# tinynumitronboard-extended.net
KiCad netlist of a schematic drawn in EAGLE
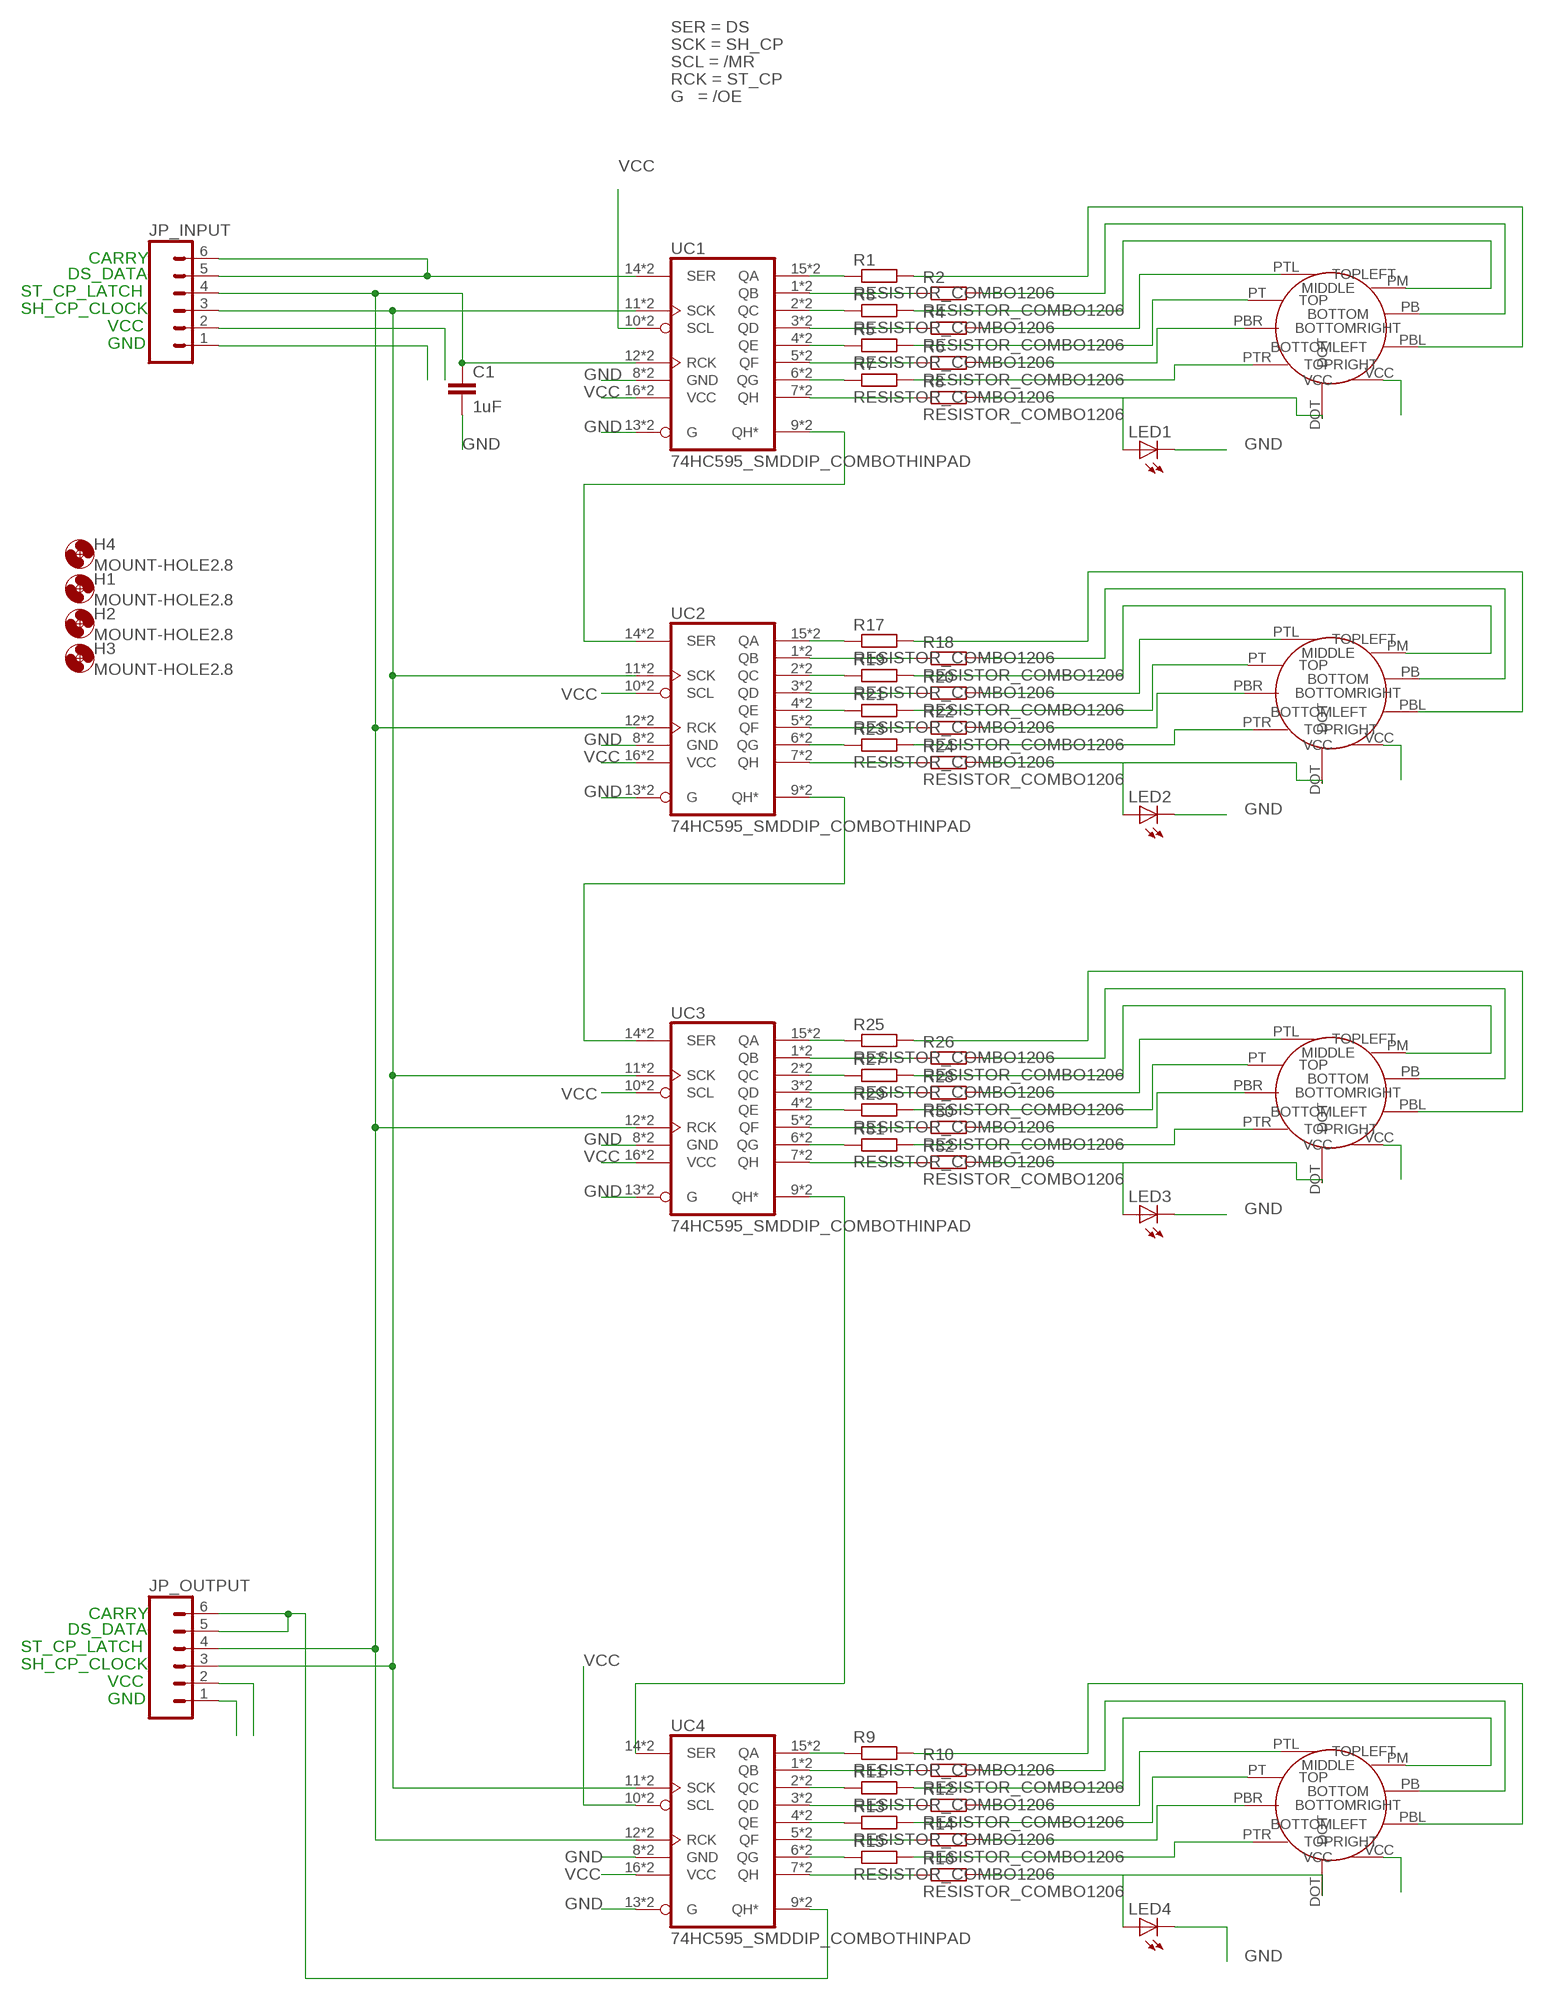
[diagram p0: schematic, sheet 1]

(export (version "E")
  (design (tool "Eeschema 10.0.6"))
  (components
    (comp (ref "C1")
      (value "1uF")
      (footprint "eagle-import:C050-024X044")
      (libsource (lib "eagle-import") (part "C-EU050-024X044"))
    )
    (comp (ref "H1")
      (value "MOUNT-HOLE2.8")
      (footprint "eagle-import:2,8")
      (libsource (lib "eagle-import") (part "MOUNT-HOLE2.8"))
    )
    (comp (ref "H2")
      (value "MOUNT-HOLE2.8")
      (footprint "eagle-import:2,8")
      (libsource (lib "eagle-import") (part "MOUNT-HOLE2.8"))
    )
    (comp (ref "H3")
      (value "MOUNT-HOLE2.8")
      (footprint "eagle-import:2,8")
      (libsource (lib "eagle-import") (part "MOUNT-HOLE2.8"))
    )
    (comp (ref "H4")
      (value "MOUNT-HOLE2.8")
      (footprint "eagle-import:2,8")
      (libsource (lib "eagle-import") (part "MOUNT-HOLE2.8"))
    )
    (comp (ref "JP_INPUT")
      (value "M06SIP")
      (footprint "eagle-import:1X06")
      (libsource (lib "eagle-import") (part "M06SIP"))
    )
    (comp (ref "JP_OUTPUT")
      (value "M06SIP")
      (footprint "eagle-import:1X06")
      (libsource (lib "eagle-import") (part "M06SIP"))
    )
    (comp (ref "LED1")
      (value "LEDKA-3528ASYC")
      (footprint "eagle-import:KA-3528ASYC")
      (libsource (lib "eagle-import") (part "LEDKA-3528ASYC"))
    )
    (comp (ref "LED2")
      (value "LEDKA-3528ASYC")
      (footprint "eagle-import:KA-3528ASYC")
      (libsource (lib "eagle-import") (part "LEDKA-3528ASYC"))
    )
    (comp (ref "LED3")
      (value "LEDKA-3528ASYC")
      (footprint "eagle-import:KA-3528ASYC")
      (libsource (lib "eagle-import") (part "LEDKA-3528ASYC"))
    )
    (comp (ref "LED4")
      (value "LEDKA-3528ASYC")
      (footprint "eagle-import:KA-3528ASYC")
      (libsource (lib "eagle-import") (part "LEDKA-3528ASYC"))
    )
    (comp (ref "R1")
      (value "RESISTOR_COMBO1206")
      (footprint "eagle-import:207-10_SMD_COMBO")
      (libsource (lib "eagle-import") (part "RESISTOR_COMBO1206"))
    )
    (comp (ref "R2")
      (value "RESISTOR_COMBO1206")
      (footprint "eagle-import:207-10_SMD_COMBO")
      (libsource (lib "eagle-import") (part "RESISTOR_COMBO1206"))
    )
    (comp (ref "R3")
      (value "RESISTOR_COMBO1206")
      (footprint "eagle-import:207-10_SMD_COMBO")
      (libsource (lib "eagle-import") (part "RESISTOR_COMBO1206"))
    )
    (comp (ref "R4")
      (value "RESISTOR_COMBO1206")
      (footprint "eagle-import:207-10_SMD_COMBO")
      (libsource (lib "eagle-import") (part "RESISTOR_COMBO1206"))
    )
    (comp (ref "R5")
      (value "RESISTOR_COMBO1206")
      (footprint "eagle-import:207-10_SMD_COMBO")
      (libsource (lib "eagle-import") (part "RESISTOR_COMBO1206"))
    )
    (comp (ref "R6")
      (value "RESISTOR_COMBO1206")
      (footprint "eagle-import:207-10_SMD_COMBO")
      (libsource (lib "eagle-import") (part "RESISTOR_COMBO1206"))
    )
    (comp (ref "R7")
      (value "RESISTOR_COMBO1206")
      (footprint "eagle-import:207-10_SMD_COMBO")
      (libsource (lib "eagle-import") (part "RESISTOR_COMBO1206"))
    )
    (comp (ref "R8")
      (value "RESISTOR_COMBO1206")
      (footprint "eagle-import:207-10_SMD_COMBO")
      (libsource (lib "eagle-import") (part "RESISTOR_COMBO1206"))
    )
    (comp (ref "R9")
      (value "RESISTOR_COMBO1206")
      (footprint "eagle-import:207-10_SMD_COMBO")
      (libsource (lib "eagle-import") (part "RESISTOR_COMBO1206"))
    )
    (comp (ref "R10")
      (value "RESISTOR_COMBO1206")
      (footprint "eagle-import:207-10_SMD_COMBO")
      (libsource (lib "eagle-import") (part "RESISTOR_COMBO1206"))
    )
    (comp (ref "R11")
      (value "RESISTOR_COMBO1206")
      (footprint "eagle-import:207-10_SMD_COMBO")
      (libsource (lib "eagle-import") (part "RESISTOR_COMBO1206"))
    )
    (comp (ref "R12")
      (value "RESISTOR_COMBO1206")
      (footprint "eagle-import:207-10_SMD_COMBO")
      (libsource (lib "eagle-import") (part "RESISTOR_COMBO1206"))
    )
    (comp (ref "R13")
      (value "RESISTOR_COMBO1206")
      (footprint "eagle-import:207-10_SMD_COMBO")
      (libsource (lib "eagle-import") (part "RESISTOR_COMBO1206"))
    )
    (comp (ref "R14")
      (value "RESISTOR_COMBO1206")
      (footprint "eagle-import:207-10_SMD_COMBO")
      (libsource (lib "eagle-import") (part "RESISTOR_COMBO1206"))
    )
    (comp (ref "R15")
      (value "RESISTOR_COMBO1206")
      (footprint "eagle-import:207-10_SMD_COMBO")
      (libsource (lib "eagle-import") (part "RESISTOR_COMBO1206"))
    )
    (comp (ref "R16")
      (value "RESISTOR_COMBO1206")
      (footprint "eagle-import:207-10_SMD_COMBO")
      (libsource (lib "eagle-import") (part "RESISTOR_COMBO1206"))
    )
    (comp (ref "R17")
      (value "RESISTOR_COMBO1206")
      (footprint "eagle-import:207-10_SMD_COMBO")
      (libsource (lib "eagle-import") (part "RESISTOR_COMBO1206"))
    )
    (comp (ref "R18")
      (value "RESISTOR_COMBO1206")
      (footprint "eagle-import:207-10_SMD_COMBO")
      (libsource (lib "eagle-import") (part "RESISTOR_COMBO1206"))
    )
    (comp (ref "R19")
      (value "RESISTOR_COMBO1206")
      (footprint "eagle-import:207-10_SMD_COMBO")
      (libsource (lib "eagle-import") (part "RESISTOR_COMBO1206"))
    )
    (comp (ref "R20")
      (value "RESISTOR_COMBO1206")
      (footprint "eagle-import:207-10_SMD_COMBO")
      (libsource (lib "eagle-import") (part "RESISTOR_COMBO1206"))
    )
    (comp (ref "R21")
      (value "RESISTOR_COMBO1206")
      (footprint "eagle-import:207-10_SMD_COMBO")
      (libsource (lib "eagle-import") (part "RESISTOR_COMBO1206"))
    )
    (comp (ref "R22")
      (value "RESISTOR_COMBO1206")
      (footprint "eagle-import:207-10_SMD_COMBO")
      (libsource (lib "eagle-import") (part "RESISTOR_COMBO1206"))
    )
    (comp (ref "R23")
      (value "RESISTOR_COMBO1206")
      (footprint "eagle-import:207-10_SMD_COMBO")
      (libsource (lib "eagle-import") (part "RESISTOR_COMBO1206"))
    )
    (comp (ref "R24")
      (value "RESISTOR_COMBO1206")
      (footprint "eagle-import:207-10_SMD_COMBO")
      (libsource (lib "eagle-import") (part "RESISTOR_COMBO1206"))
    )
    (comp (ref "R25")
      (value "RESISTOR_COMBO1206")
      (footprint "eagle-import:207-10_SMD_COMBO")
      (libsource (lib "eagle-import") (part "RESISTOR_COMBO1206"))
    )
    (comp (ref "R26")
      (value "RESISTOR_COMBO1206")
      (footprint "eagle-import:207-10_SMD_COMBO")
      (libsource (lib "eagle-import") (part "RESISTOR_COMBO1206"))
    )
    (comp (ref "R27")
      (value "RESISTOR_COMBO1206")
      (footprint "eagle-import:207-10_SMD_COMBO")
      (libsource (lib "eagle-import") (part "RESISTOR_COMBO1206"))
    )
    (comp (ref "R28")
      (value "RESISTOR_COMBO1206")
      (footprint "eagle-import:207-10_SMD_COMBO")
      (libsource (lib "eagle-import") (part "RESISTOR_COMBO1206"))
    )
    (comp (ref "R29")
      (value "RESISTOR_COMBO1206")
      (footprint "eagle-import:207-10_SMD_COMBO")
      (libsource (lib "eagle-import") (part "RESISTOR_COMBO1206"))
    )
    (comp (ref "R30")
      (value "RESISTOR_COMBO1206")
      (footprint "eagle-import:207-10_SMD_COMBO")
      (libsource (lib "eagle-import") (part "RESISTOR_COMBO1206"))
    )
    (comp (ref "R31")
      (value "RESISTOR_COMBO1206")
      (footprint "eagle-import:207-10_SMD_COMBO")
      (libsource (lib "eagle-import") (part "RESISTOR_COMBO1206"))
    )
    (comp (ref "R32")
      (value "RESISTOR_COMBO1206")
      (footprint "eagle-import:207-10_SMD_COMBO")
      (libsource (lib "eagle-import") (part "RESISTOR_COMBO1206"))
    )
    (comp (ref "U$1")
      (value "IV16TINY_NUMITRON")
      (footprint "eagle-import:IV16TINY_NUMITRON_PAC")
      (libsource (lib "eagle-import") (part "IV16TINY_NUMITRON"))
    )
    (comp (ref "U$2")
      (value "IV16TINY_NUMITRON")
      (footprint "eagle-import:IV16TINY_NUMITRON_PAC")
      (libsource (lib "eagle-import") (part "IV16TINY_NUMITRON"))
    )
    (comp (ref "U$5")
      (value "IV16TINY_NUMITRON")
      (footprint "eagle-import:IV16TINY_NUMITRON_PAC")
      (libsource (lib "eagle-import") (part "IV16TINY_NUMITRON"))
    )
    (comp (ref "U$7")
      (value "IV16TINY_NUMITRON")
      (footprint "eagle-import:IV16TINY_NUMITRON_PAC")
      (libsource (lib "eagle-import") (part "IV16TINY_NUMITRON"))
    )
    (comp (ref "UC1")
      (value "74HC595_SMDDIP_COMBOTHINPAD")
      (footprint "eagle-import:DIL16_SO16_PAC2")
      (libsource (lib "eagle-import") (part "74HC595_SMDDIP_COMBOTHINPAD"))
    )
    (comp (ref "UC2")
      (value "74HC595_SMDDIP_COMBOTHINPAD")
      (footprint "eagle-import:DIL16_SO16_PAC2")
      (libsource (lib "eagle-import") (part "74HC595_SMDDIP_COMBOTHINPAD"))
    )
    (comp (ref "UC3")
      (value "74HC595_SMDDIP_COMBOTHINPAD")
      (footprint "eagle-import:DIL16_SO16_PAC2")
      (libsource (lib "eagle-import") (part "74HC595_SMDDIP_COMBOTHINPAD"))
    )
    (comp (ref "UC4")
      (value "74HC595_SMDDIP_COMBOTHINPAD")
      (footprint "eagle-import:DIL16_SO16_PAC2")
      (libsource (lib "eagle-import") (part "74HC595_SMDDIP_COMBOTHINPAD"))
    )
  )
  (nets
    (net (code "1") (name "/GND") (class "Default")
      (node (ref "C1") (pin "2") (pinfunction "2_2") (pintype "passive"))
      (node (ref "JP_INPUT") (pin "1") (pinfunction "1_1") (pintype "passive"))
      (node (ref "JP_OUTPUT") (pin "1") (pinfunction "1_1") (pintype "passive"))
      (node (ref "LED1") (pin "C") (pinfunction "C_C") (pintype "passive"))
      (node (ref "LED2") (pin "C") (pinfunction "C_C") (pintype "passive"))
      (node (ref "LED3") (pin "C") (pinfunction "C_C") (pintype "passive"))
      (node (ref "LED4") (pin "C") (pinfunction "C_C") (pintype "passive"))
      (node (ref "UC1") (pin "13") (pinfunction "G_13") (pintype "input"))
      (node (ref "UC1") (pin "8") (pinfunction "GND_8") (pintype "power_in"))
      (node (ref "UC1") (pin "S13") (pinfunction "G_S13") (pintype "input"))
      (node (ref "UC1") (pin "S8") (pinfunction "GND_S8") (pintype "power_in"))
      (node (ref "UC2") (pin "13") (pinfunction "G_13") (pintype "input"))
      (node (ref "UC2") (pin "8") (pinfunction "GND_8") (pintype "power_in"))
      (node (ref "UC2") (pin "S13") (pinfunction "G_S13") (pintype "input"))
      (node (ref "UC2") (pin "S8") (pinfunction "GND_S8") (pintype "power_in"))
      (node (ref "UC3") (pin "13") (pinfunction "G_13") (pintype "input"))
      (node (ref "UC3") (pin "8") (pinfunction "GND_8") (pintype "power_in"))
      (node (ref "UC3") (pin "S13") (pinfunction "G_S13") (pintype "input"))
      (node (ref "UC3") (pin "S8") (pinfunction "GND_S8") (pintype "power_in"))
      (node (ref "UC4") (pin "13") (pinfunction "G_13") (pintype "input"))
      (node (ref "UC4") (pin "8") (pinfunction "GND_8") (pintype "power_in"))
      (node (ref "UC4") (pin "S13") (pinfunction "G_S13") (pintype "input"))
      (node (ref "UC4") (pin "S8") (pinfunction "GND_S8") (pintype "power_in"))
    )
    (net (code "2") (name "/VCC") (class "Default")
      (node (ref "JP_INPUT") (pin "2") (pinfunction "2_2") (pintype "passive"))
      (node (ref "JP_OUTPUT") (pin "2") (pinfunction "2_2") (pintype "passive"))
      (node (ref "U$1") (pin "VCC") (pinfunction "VCC_VCC") (pintype "input"))
      (node (ref "U$2") (pin "VCC") (pinfunction "VCC_VCC") (pintype "input"))
      (node (ref "U$5") (pin "VCC") (pinfunction "VCC_VCC") (pintype "input"))
      (node (ref "U$7") (pin "VCC") (pinfunction "VCC_VCC") (pintype "input"))
      (node (ref "UC1") (pin "10") (pinfunction "SCL_10") (pintype "input"))
      (node (ref "UC1") (pin "16") (pinfunction "VCC_16") (pintype "power_in"))
      (node (ref "UC1") (pin "S10") (pinfunction "SCL_S10") (pintype "input"))
      (node (ref "UC1") (pin "S16") (pinfunction "VCC_S16") (pintype "power_in"))
      (node (ref "UC2") (pin "10") (pinfunction "SCL_10") (pintype "input"))
      (node (ref "UC2") (pin "16") (pinfunction "VCC_16") (pintype "power_in"))
      (node (ref "UC2") (pin "S10") (pinfunction "SCL_S10") (pintype "input"))
      (node (ref "UC2") (pin "S16") (pinfunction "VCC_S16") (pintype "power_in"))
      (node (ref "UC3") (pin "10") (pinfunction "SCL_10") (pintype "input"))
      (node (ref "UC3") (pin "16") (pinfunction "VCC_16") (pintype "power_in"))
      (node (ref "UC3") (pin "S10") (pinfunction "SCL_S10") (pintype "input"))
      (node (ref "UC3") (pin "S16") (pinfunction "VCC_S16") (pintype "power_in"))
      (node (ref "UC4") (pin "10") (pinfunction "SCL_10") (pintype "input"))
      (node (ref "UC4") (pin "16") (pinfunction "VCC_16") (pintype "power_in"))
      (node (ref "UC4") (pin "S10") (pinfunction "SCL_S10") (pintype "input"))
      (node (ref "UC4") (pin "S16") (pinfunction "VCC_S16") (pintype "power_in"))
    )
    (net (code "3") (name "Net-(C1-Pad1)") (class "Default")
      (node (ref "C1") (pin "1") (pinfunction "1_1") (pintype "passive"))
      (node (ref "JP_INPUT") (pin "4") (pinfunction "4_4") (pintype "passive"))
      (node (ref "JP_OUTPUT") (pin "4") (pinfunction "4_4") (pintype "passive"))
      (node (ref "UC1") (pin "12") (pinfunction "RCK_12") (pintype "input"))
      (node (ref "UC1") (pin "S12") (pinfunction "RCK_S12") (pintype "input"))
      (node (ref "UC2") (pin "12") (pinfunction "RCK_12") (pintype "input"))
      (node (ref "UC2") (pin "S12") (pinfunction "RCK_S12") (pintype "input"))
      (node (ref "UC3") (pin "12") (pinfunction "RCK_12") (pintype "input"))
      (node (ref "UC3") (pin "S12") (pinfunction "RCK_S12") (pintype "input"))
      (node (ref "UC4") (pin "12") (pinfunction "RCK_12") (pintype "input"))
      (node (ref "UC4") (pin "S12") (pinfunction "RCK_S12") (pintype "input"))
    )
    (net (code "4") (name "Net-(JP_INPUT-Pad3)") (class "Default")
      (node (ref "JP_INPUT") (pin "3") (pinfunction "3_3") (pintype "passive"))
      (node (ref "JP_OUTPUT") (pin "3") (pinfunction "3_3") (pintype "passive"))
      (node (ref "UC1") (pin "11") (pinfunction "SCK_11") (pintype "input"))
      (node (ref "UC1") (pin "S11") (pinfunction "SCK_S11") (pintype "input"))
      (node (ref "UC2") (pin "11") (pinfunction "SCK_11") (pintype "input"))
      (node (ref "UC2") (pin "S11") (pinfunction "SCK_S11") (pintype "input"))
      (node (ref "UC3") (pin "11") (pinfunction "SCK_11") (pintype "input"))
      (node (ref "UC3") (pin "S11") (pinfunction "SCK_S11") (pintype "input"))
      (node (ref "UC4") (pin "11") (pinfunction "SCK_11") (pintype "input"))
      (node (ref "UC4") (pin "S11") (pinfunction "SCK_S11") (pintype "input"))
    )
    (net (code "5") (name "Net-(JP_INPUT-Pad5)") (class "Default")
      (node (ref "JP_INPUT") (pin "5") (pinfunction "5_5") (pintype "passive"))
      (node (ref "JP_INPUT") (pin "6") (pinfunction "6_6") (pintype "passive"))
      (node (ref "UC1") (pin "14") (pinfunction "SER_14") (pintype "input"))
      (node (ref "UC1") (pin "S14") (pinfunction "SER_S14") (pintype "input"))
    )
    (net (code "6") (name "Net-(JP_OUTPUT-Pad5)") (class "Default")
      (node (ref "JP_OUTPUT") (pin "5") (pinfunction "5_5") (pintype "passive"))
      (node (ref "JP_OUTPUT") (pin "6") (pinfunction "6_6") (pintype "passive"))
      (node (ref "UC4") (pin "9") (pinfunction "QH*_9") (pintype "tri_state"))
      (node (ref "UC4") (pin "S9") (pinfunction "QH*_S9") (pintype "tri_state"))
    )
    (net (code "7") (name "Net-(LED1-PadA)") (class "Default")
      (node (ref "LED1") (pin "A") (pinfunction "A_A") (pintype "passive"))
      (node (ref "R8") (pin "2") (pinfunction "2_2") (pintype "passive"))
      (node (ref "R8") (pin "3") (pinfunction "2_3") (pintype "passive"))
      (node (ref "U$1") (pin "DOT") (pinfunction "DOT_DOT") (pintype "bidirectional"))
    )
    (net (code "8") (name "Net-(LED2-PadA)") (class "Default")
      (node (ref "LED2") (pin "A") (pinfunction "A_A") (pintype "passive"))
      (node (ref "R24") (pin "2") (pinfunction "2_2") (pintype "passive"))
      (node (ref "R24") (pin "3") (pinfunction "2_3") (pintype "passive"))
      (node (ref "U$5") (pin "DOT") (pinfunction "DOT_DOT") (pintype "bidirectional"))
    )
    (net (code "9") (name "Net-(LED3-PadA)") (class "Default")
      (node (ref "LED3") (pin "A") (pinfunction "A_A") (pintype "passive"))
      (node (ref "R32") (pin "2") (pinfunction "2_2") (pintype "passive"))
      (node (ref "R32") (pin "3") (pinfunction "2_3") (pintype "passive"))
      (node (ref "U$7") (pin "DOT") (pinfunction "DOT_DOT") (pintype "bidirectional"))
    )
    (net (code "10") (name "Net-(LED4-PadA)") (class "Default")
      (node (ref "LED4") (pin "A") (pinfunction "A_A") (pintype "passive"))
      (node (ref "R16") (pin "2") (pinfunction "2_2") (pintype "passive"))
      (node (ref "R16") (pin "3") (pinfunction "2_3") (pintype "passive"))
      (node (ref "U$2") (pin "DOT") (pinfunction "DOT_DOT") (pintype "bidirectional"))
    )
    (net (code "11") (name "Net-(R1-1-Pad4)") (class "Default")
      (node (ref "R1") (pin "1") (pinfunction "1_1") (pintype "passive"))
      (node (ref "R1") (pin "4") (pinfunction "1_4") (pintype "passive"))
      (node (ref "UC1") (pin "15") (pinfunction "QA_15") (pintype "tri_state"))
      (node (ref "UC1") (pin "S15") (pinfunction "QA_S15") (pintype "tri_state"))
    )
    (net (code "12") (name "Net-(R2-1-Pad4)") (class "Default")
      (node (ref "R2") (pin "1") (pinfunction "1_1") (pintype "passive"))
      (node (ref "R2") (pin "4") (pinfunction "1_4") (pintype "passive"))
      (node (ref "UC1") (pin "1") (pinfunction "QB_1") (pintype "tri_state"))
      (node (ref "UC1") (pin "S1") (pinfunction "QB_S1") (pintype "tri_state"))
    )
    (net (code "13") (name "Net-(R3-1-Pad4)") (class "Default")
      (node (ref "R3") (pin "1") (pinfunction "1_1") (pintype "passive"))
      (node (ref "R3") (pin "4") (pinfunction "1_4") (pintype "passive"))
      (node (ref "UC1") (pin "2") (pinfunction "QC_2") (pintype "tri_state"))
      (node (ref "UC1") (pin "S2") (pinfunction "QC_S2") (pintype "tri_state"))
    )
    (net (code "14") (name "Net-(R4-1-Pad4)") (class "Default")
      (node (ref "R4") (pin "1") (pinfunction "1_1") (pintype "passive"))
      (node (ref "R4") (pin "4") (pinfunction "1_4") (pintype "passive"))
      (node (ref "UC1") (pin "3") (pinfunction "QD_3") (pintype "tri_state"))
      (node (ref "UC1") (pin "S3") (pinfunction "QD_S3") (pintype "tri_state"))
    )
    (net (code "15") (name "Net-(R5-1-Pad4)") (class "Default")
      (node (ref "R5") (pin "1") (pinfunction "1_1") (pintype "passive"))
      (node (ref "R5") (pin "4") (pinfunction "1_4") (pintype "passive"))
      (node (ref "UC1") (pin "4") (pinfunction "QE_4") (pintype "tri_state"))
      (node (ref "UC1") (pin "S4") (pinfunction "QE_S4") (pintype "tri_state"))
    )
    (net (code "16") (name "Net-(R6-1-Pad4)") (class "Default")
      (node (ref "R6") (pin "1") (pinfunction "1_1") (pintype "passive"))
      (node (ref "R6") (pin "4") (pinfunction "1_4") (pintype "passive"))
      (node (ref "UC1") (pin "5") (pinfunction "QF_5") (pintype "tri_state"))
      (node (ref "UC1") (pin "S5") (pinfunction "QF_S5") (pintype "tri_state"))
    )
    (net (code "17") (name "Net-(R7-1-Pad4)") (class "Default")
      (node (ref "R7") (pin "1") (pinfunction "1_1") (pintype "passive"))
      (node (ref "R7") (pin "4") (pinfunction "1_4") (pintype "passive"))
      (node (ref "UC1") (pin "6") (pinfunction "QG_6") (pintype "tri_state"))
      (node (ref "UC1") (pin "S6") (pinfunction "QG_S6") (pintype "tri_state"))
    )
    (net (code "18") (name "Net-(R8-1-Pad4)") (class "Default")
      (node (ref "R8") (pin "1") (pinfunction "1_1") (pintype "passive"))
      (node (ref "R8") (pin "4") (pinfunction "1_4") (pintype "passive"))
      (node (ref "UC1") (pin "7") (pinfunction "QH_7") (pintype "tri_state"))
      (node (ref "UC1") (pin "S7") (pinfunction "QH_S7") (pintype "tri_state"))
    )
    (net (code "19") (name "Net-(R9-1-Pad4)") (class "Default")
      (node (ref "R9") (pin "1") (pinfunction "1_1") (pintype "passive"))
      (node (ref "R9") (pin "4") (pinfunction "1_4") (pintype "passive"))
      (node (ref "UC4") (pin "15") (pinfunction "QA_15") (pintype "tri_state"))
      (node (ref "UC4") (pin "S15") (pinfunction "QA_S15") (pintype "tri_state"))
    )
    (net (code "20") (name "Net-(R10-1-Pad4)") (class "Default")
      (node (ref "R10") (pin "1") (pinfunction "1_1") (pintype "passive"))
      (node (ref "R10") (pin "4") (pinfunction "1_4") (pintype "passive"))
      (node (ref "UC4") (pin "1") (pinfunction "QB_1") (pintype "tri_state"))
      (node (ref "UC4") (pin "S1") (pinfunction "QB_S1") (pintype "tri_state"))
    )
    (net (code "21") (name "Net-(R11-1-Pad4)") (class "Default")
      (node (ref "R11") (pin "1") (pinfunction "1_1") (pintype "passive"))
      (node (ref "R11") (pin "4") (pinfunction "1_4") (pintype "passive"))
      (node (ref "UC4") (pin "2") (pinfunction "QC_2") (pintype "tri_state"))
      (node (ref "UC4") (pin "S2") (pinfunction "QC_S2") (pintype "tri_state"))
    )
    (net (code "22") (name "Net-(R12-1-Pad4)") (class "Default")
      (node (ref "R12") (pin "1") (pinfunction "1_1") (pintype "passive"))
      (node (ref "R12") (pin "4") (pinfunction "1_4") (pintype "passive"))
      (node (ref "UC4") (pin "3") (pinfunction "QD_3") (pintype "tri_state"))
      (node (ref "UC4") (pin "S3") (pinfunction "QD_S3") (pintype "tri_state"))
    )
    (net (code "23") (name "Net-(R13-1-Pad4)") (class "Default")
      (node (ref "R13") (pin "1") (pinfunction "1_1") (pintype "passive"))
      (node (ref "R13") (pin "4") (pinfunction "1_4") (pintype "passive"))
      (node (ref "UC4") (pin "4") (pinfunction "QE_4") (pintype "tri_state"))
      (node (ref "UC4") (pin "S4") (pinfunction "QE_S4") (pintype "tri_state"))
    )
    (net (code "24") (name "Net-(R14-1-Pad4)") (class "Default")
      (node (ref "R14") (pin "1") (pinfunction "1_1") (pintype "passive"))
      (node (ref "R14") (pin "4") (pinfunction "1_4") (pintype "passive"))
      (node (ref "UC4") (pin "5") (pinfunction "QF_5") (pintype "tri_state"))
      (node (ref "UC4") (pin "S5") (pinfunction "QF_S5") (pintype "tri_state"))
    )
    (net (code "25") (name "Net-(R15-1-Pad4)") (class "Default")
      (node (ref "R15") (pin "1") (pinfunction "1_1") (pintype "passive"))
      (node (ref "R15") (pin "4") (pinfunction "1_4") (pintype "passive"))
      (node (ref "UC4") (pin "6") (pinfunction "QG_6") (pintype "tri_state"))
      (node (ref "UC4") (pin "S6") (pinfunction "QG_S6") (pintype "tri_state"))
    )
    (net (code "26") (name "Net-(R16-1-Pad4)") (class "Default")
      (node (ref "R16") (pin "1") (pinfunction "1_1") (pintype "passive"))
      (node (ref "R16") (pin "4") (pinfunction "1_4") (pintype "passive"))
      (node (ref "UC4") (pin "7") (pinfunction "QH_7") (pintype "tri_state"))
      (node (ref "UC4") (pin "S7") (pinfunction "QH_S7") (pintype "tri_state"))
    )
    (net (code "27") (name "Net-(R17-1-Pad4)") (class "Default")
      (node (ref "R17") (pin "1") (pinfunction "1_1") (pintype "passive"))
      (node (ref "R17") (pin "4") (pinfunction "1_4") (pintype "passive"))
      (node (ref "UC2") (pin "15") (pinfunction "QA_15") (pintype "tri_state"))
      (node (ref "UC2") (pin "S15") (pinfunction "QA_S15") (pintype "tri_state"))
    )
    (net (code "28") (name "Net-(R18-1-Pad4)") (class "Default")
      (node (ref "R18") (pin "1") (pinfunction "1_1") (pintype "passive"))
      (node (ref "R18") (pin "4") (pinfunction "1_4") (pintype "passive"))
      (node (ref "UC2") (pin "1") (pinfunction "QB_1") (pintype "tri_state"))
      (node (ref "UC2") (pin "S1") (pinfunction "QB_S1") (pintype "tri_state"))
    )
    (net (code "29") (name "Net-(R19-1-Pad4)") (class "Default")
      (node (ref "R19") (pin "1") (pinfunction "1_1") (pintype "passive"))
      (node (ref "R19") (pin "4") (pinfunction "1_4") (pintype "passive"))
      (node (ref "UC2") (pin "2") (pinfunction "QC_2") (pintype "tri_state"))
      (node (ref "UC2") (pin "S2") (pinfunction "QC_S2") (pintype "tri_state"))
    )
    (net (code "30") (name "Net-(R20-1-Pad4)") (class "Default")
      (node (ref "R20") (pin "1") (pinfunction "1_1") (pintype "passive"))
      (node (ref "R20") (pin "4") (pinfunction "1_4") (pintype "passive"))
      (node (ref "UC2") (pin "3") (pinfunction "QD_3") (pintype "tri_state"))
      (node (ref "UC2") (pin "S3") (pinfunction "QD_S3") (pintype "tri_state"))
    )
    (net (code "31") (name "Net-(R21-1-Pad4)") (class "Default")
      (node (ref "R21") (pin "1") (pinfunction "1_1") (pintype "passive"))
      (node (ref "R21") (pin "4") (pinfunction "1_4") (pintype "passive"))
      (node (ref "UC2") (pin "4") (pinfunction "QE_4") (pintype "tri_state"))
      (node (ref "UC2") (pin "S4") (pinfunction "QE_S4") (pintype "tri_state"))
    )
    (net (code "32") (name "Net-(R22-1-Pad4)") (class "Default")
      (node (ref "R22") (pin "1") (pinfunction "1_1") (pintype "passive"))
      (node (ref "R22") (pin "4") (pinfunction "1_4") (pintype "passive"))
      (node (ref "UC2") (pin "5") (pinfunction "QF_5") (pintype "tri_state"))
      (node (ref "UC2") (pin "S5") (pinfunction "QF_S5") (pintype "tri_state"))
    )
    (net (code "33") (name "Net-(R23-1-Pad4)") (class "Default")
      (node (ref "R23") (pin "1") (pinfunction "1_1") (pintype "passive"))
      (node (ref "R23") (pin "4") (pinfunction "1_4") (pintype "passive"))
      (node (ref "UC2") (pin "6") (pinfunction "QG_6") (pintype "tri_state"))
      (node (ref "UC2") (pin "S6") (pinfunction "QG_S6") (pintype "tri_state"))
    )
    (net (code "34") (name "Net-(R24-1-Pad4)") (class "Default")
      (node (ref "R24") (pin "1") (pinfunction "1_1") (pintype "passive"))
      (node (ref "R24") (pin "4") (pinfunction "1_4") (pintype "passive"))
      (node (ref "UC2") (pin "7") (pinfunction "QH_7") (pintype "tri_state"))
      (node (ref "UC2") (pin "S7") (pinfunction "QH_S7") (pintype "tri_state"))
    )
    (net (code "35") (name "Net-(R25-1-Pad4)") (class "Default")
      (node (ref "R25") (pin "1") (pinfunction "1_1") (pintype "passive"))
      (node (ref "R25") (pin "4") (pinfunction "1_4") (pintype "passive"))
      (node (ref "UC3") (pin "15") (pinfunction "QA_15") (pintype "tri_state"))
      (node (ref "UC3") (pin "S15") (pinfunction "QA_S15") (pintype "tri_state"))
    )
    (net (code "36") (name "Net-(R26-1-Pad4)") (class "Default")
      (node (ref "R26") (pin "1") (pinfunction "1_1") (pintype "passive"))
      (node (ref "R26") (pin "4") (pinfunction "1_4") (pintype "passive"))
      (node (ref "UC3") (pin "1") (pinfunction "QB_1") (pintype "tri_state"))
      (node (ref "UC3") (pin "S1") (pinfunction "QB_S1") (pintype "tri_state"))
    )
    (net (code "37") (name "Net-(R27-1-Pad4)") (class "Default")
      (node (ref "R27") (pin "1") (pinfunction "1_1") (pintype "passive"))
      (node (ref "R27") (pin "4") (pinfunction "1_4") (pintype "passive"))
      (node (ref "UC3") (pin "2") (pinfunction "QC_2") (pintype "tri_state"))
      (node (ref "UC3") (pin "S2") (pinfunction "QC_S2") (pintype "tri_state"))
    )
    (net (code "38") (name "Net-(R28-1-Pad4)") (class "Default")
      (node (ref "R28") (pin "1") (pinfunction "1_1") (pintype "passive"))
      (node (ref "R28") (pin "4") (pinfunction "1_4") (pintype "passive"))
      (node (ref "UC3") (pin "3") (pinfunction "QD_3") (pintype "tri_state"))
      (node (ref "UC3") (pin "S3") (pinfunction "QD_S3") (pintype "tri_state"))
    )
    (net (code "39") (name "Net-(R29-1-Pad4)") (class "Default")
      (node (ref "R29") (pin "1") (pinfunction "1_1") (pintype "passive"))
      (node (ref "R29") (pin "4") (pinfunction "1_4") (pintype "passive"))
      (node (ref "UC3") (pin "4") (pinfunction "QE_4") (pintype "tri_state"))
      (node (ref "UC3") (pin "S4") (pinfunction "QE_S4") (pintype "tri_state"))
    )
    (net (code "40") (name "Net-(R30-1-Pad4)") (class "Default")
      (node (ref "R30") (pin "1") (pinfunction "1_1") (pintype "passive"))
      (node (ref "R30") (pin "4") (pinfunction "1_4") (pintype "passive"))
      (node (ref "UC3") (pin "5") (pinfunction "QF_5") (pintype "tri_state"))
      (node (ref "UC3") (pin "S5") (pinfunction "QF_S5") (pintype "tri_state"))
    )
    (net (code "41") (name "Net-(R31-1-Pad4)") (class "Default")
      (node (ref "R31") (pin "1") (pinfunction "1_1") (pintype "passive"))
      (node (ref "R31") (pin "4") (pinfunction "1_4") (pintype "passive"))
      (node (ref "UC3") (pin "6") (pinfunction "QG_6") (pintype "tri_state"))
      (node (ref "UC3") (pin "S6") (pinfunction "QG_S6") (pintype "tri_state"))
    )
    (net (code "42") (name "Net-(R32-1-Pad4)") (class "Default")
      (node (ref "R32") (pin "1") (pinfunction "1_1") (pintype "passive"))
      (node (ref "R32") (pin "4") (pinfunction "1_4") (pintype "passive"))
      (node (ref "UC3") (pin "7") (pinfunction "QH_7") (pintype "tri_state"))
      (node (ref "UC3") (pin "S7") (pinfunction "QH_S7") (pintype "tri_state"))
    )
    (net (code "43") (name "Net-(U$1-BOTTOM)") (class "Default")
      (node (ref "R2") (pin "2") (pinfunction "2_2") (pintype "passive"))
      (node (ref "R2") (pin "3") (pinfunction "2_3") (pintype "passive"))
      (node (ref "U$1") (pin "PB") (pinfunction "BOTTOM_PB") (pintype "input"))
    )
    (net (code "44") (name "Net-(U$1-BOTTOMLEFT)") (class "Default")
      (node (ref "R1") (pin "2") (pinfunction "2_2") (pintype "passive"))
      (node (ref "R1") (pin "3") (pinfunction "2_3") (pintype "passive"))
      (node (ref "U$1") (pin "PBL") (pinfunction "BOTTOMLEFT_PBL") (pintype "input"))
    )
    (net (code "45") (name "Net-(U$1-BOTTOMRIGHT)") (class "Default")
      (node (ref "R6") (pin "2") (pinfunction "2_2") (pintype "passive"))
      (node (ref "R6") (pin "3") (pinfunction "2_3") (pintype "passive"))
      (node (ref "U$1") (pin "PBR") (pinfunction "BOTTOMRIGHT_PBR") (pintype "input"))
    )
    (net (code "46") (name "Net-(U$1-MIDDLE)") (class "Default")
      (node (ref "R3") (pin "2") (pinfunction "2_2") (pintype "passive"))
      (node (ref "R3") (pin "3") (pinfunction "2_3") (pintype "passive"))
      (node (ref "U$1") (pin "PM") (pinfunction "MIDDLE_PM") (pintype "input"))
    )
    (net (code "47") (name "Net-(U$1-TOP)") (class "Default")
      (node (ref "R5") (pin "2") (pinfunction "2_2") (pintype "passive"))
      (node (ref "R5") (pin "3") (pinfunction "2_3") (pintype "passive"))
      (node (ref "U$1") (pin "PT") (pinfunction "TOP_PT") (pintype "input"))
    )
    (net (code "48") (name "Net-(U$1-TOPLEFT)") (class "Default")
      (node (ref "R4") (pin "2") (pinfunction "2_2") (pintype "passive"))
      (node (ref "R4") (pin "3") (pinfunction "2_3") (pintype "passive"))
      (node (ref "U$1") (pin "PTL") (pinfunction "TOPLEFT_PTL") (pintype "input"))
    )
    (net (code "49") (name "Net-(U$1-TOPRIGHT)") (class "Default")
      (node (ref "R7") (pin "2") (pinfunction "2_2") (pintype "passive"))
      (node (ref "R7") (pin "3") (pinfunction "2_3") (pintype "passive"))
      (node (ref "U$1") (pin "PTR") (pinfunction "TOPRIGHT_PTR") (pintype "input"))
    )
    (net (code "50") (name "Net-(U$2-BOTTOM)") (class "Default")
      (node (ref "R10") (pin "2") (pinfunction "2_2") (pintype "passive"))
      (node (ref "R10") (pin "3") (pinfunction "2_3") (pintype "passive"))
      (node (ref "U$2") (pin "PB") (pinfunction "BOTTOM_PB") (pintype "input"))
    )
    (net (code "51") (name "Net-(U$2-BOTTOMLEFT)") (class "Default")
      (node (ref "R9") (pin "2") (pinfunction "2_2") (pintype "passive"))
      (node (ref "R9") (pin "3") (pinfunction "2_3") (pintype "passive"))
      (node (ref "U$2") (pin "PBL") (pinfunction "BOTTOMLEFT_PBL") (pintype "input"))
    )
    (net (code "52") (name "Net-(U$2-BOTTOMRIGHT)") (class "Default")
      (node (ref "R14") (pin "2") (pinfunction "2_2") (pintype "passive"))
      (node (ref "R14") (pin "3") (pinfunction "2_3") (pintype "passive"))
      (node (ref "U$2") (pin "PBR") (pinfunction "BOTTOMRIGHT_PBR") (pintype "input"))
    )
    (net (code "53") (name "Net-(U$2-MIDDLE)") (class "Default")
      (node (ref "R11") (pin "2") (pinfunction "2_2") (pintype "passive"))
      (node (ref "R11") (pin "3") (pinfunction "2_3") (pintype "passive"))
      (node (ref "U$2") (pin "PM") (pinfunction "MIDDLE_PM") (pintype "input"))
    )
    (net (code "54") (name "Net-(U$2-TOP)") (class "Default")
      (node (ref "R13") (pin "2") (pinfunction "2_2") (pintype "passive"))
      (node (ref "R13") (pin "3") (pinfunction "2_3") (pintype "passive"))
      (node (ref "U$2") (pin "PT") (pinfunction "TOP_PT") (pintype "input"))
    )
    (net (code "55") (name "Net-(U$2-TOPLEFT)") (class "Default")
      (node (ref "R12") (pin "2") (pinfunction "2_2") (pintype "passive"))
      (node (ref "R12") (pin "3") (pinfunction "2_3") (pintype "passive"))
      (node (ref "U$2") (pin "PTL") (pinfunction "TOPLEFT_PTL") (pintype "input"))
    )
    (net (code "56") (name "Net-(U$2-TOPRIGHT)") (class "Default")
      (node (ref "R15") (pin "2") (pinfunction "2_2") (pintype "passive"))
      (node (ref "R15") (pin "3") (pinfunction "2_3") (pintype "passive"))
      (node (ref "U$2") (pin "PTR") (pinfunction "TOPRIGHT_PTR") (pintype "input"))
    )
    (net (code "57") (name "Net-(U$5-BOTTOM)") (class "Default")
      (node (ref "R18") (pin "2") (pinfunction "2_2") (pintype "passive"))
      (node (ref "R18") (pin "3") (pinfunction "2_3") (pintype "passive"))
      (node (ref "U$5") (pin "PB") (pinfunction "BOTTOM_PB") (pintype "input"))
    )
    (net (code "58") (name "Net-(U$5-BOTTOMLEFT)") (class "Default")
      (node (ref "R17") (pin "2") (pinfunction "2_2") (pintype "passive"))
      (node (ref "R17") (pin "3") (pinfunction "2_3") (pintype "passive"))
      (node (ref "U$5") (pin "PBL") (pinfunction "BOTTOMLEFT_PBL") (pintype "input"))
    )
    (net (code "59") (name "Net-(U$5-BOTTOMRIGHT)") (class "Default")
      (node (ref "R22") (pin "2") (pinfunction "2_2") (pintype "passive"))
      (node (ref "R22") (pin "3") (pinfunction "2_3") (pintype "passive"))
      (node (ref "U$5") (pin "PBR") (pinfunction "BOTTOMRIGHT_PBR") (pintype "input"))
    )
    (net (code "60") (name "Net-(U$5-MIDDLE)") (class "Default")
      (node (ref "R19") (pin "2") (pinfunction "2_2") (pintype "passive"))
      (node (ref "R19") (pin "3") (pinfunction "2_3") (pintype "passive"))
      (node (ref "U$5") (pin "PM") (pinfunction "MIDDLE_PM") (pintype "input"))
    )
    (net (code "61") (name "Net-(U$5-TOP)") (class "Default")
      (node (ref "R21") (pin "2") (pinfunction "2_2") (pintype "passive"))
      (node (ref "R21") (pin "3") (pinfunction "2_3") (pintype "passive"))
      (node (ref "U$5") (pin "PT") (pinfunction "TOP_PT") (pintype "input"))
    )
    (net (code "62") (name "Net-(U$5-TOPLEFT)") (class "Default")
      (node (ref "R20") (pin "2") (pinfunction "2_2") (pintype "passive"))
      (node (ref "R20") (pin "3") (pinfunction "2_3") (pintype "passive"))
      (node (ref "U$5") (pin "PTL") (pinfunction "TOPLEFT_PTL") (pintype "input"))
    )
    (net (code "63") (name "Net-(U$5-TOPRIGHT)") (class "Default")
      (node (ref "R23") (pin "2") (pinfunction "2_2") (pintype "passive"))
      (node (ref "R23") (pin "3") (pinfunction "2_3") (pintype "passive"))
      (node (ref "U$5") (pin "PTR") (pinfunction "TOPRIGHT_PTR") (pintype "input"))
    )
    (net (code "64") (name "Net-(U$7-BOTTOM)") (class "Default")
      (node (ref "R26") (pin "2") (pinfunction "2_2") (pintype "passive"))
      (node (ref "R26") (pin "3") (pinfunction "2_3") (pintype "passive"))
      (node (ref "U$7") (pin "PB") (pinfunction "BOTTOM_PB") (pintype "input"))
    )
    (net (code "65") (name "Net-(U$7-BOTTOMLEFT)") (class "Default")
      (node (ref "R25") (pin "2") (pinfunction "2_2") (pintype "passive"))
      (node (ref "R25") (pin "3") (pinfunction "2_3") (pintype "passive"))
      (node (ref "U$7") (pin "PBL") (pinfunction "BOTTOMLEFT_PBL") (pintype "input"))
    )
    (net (code "66") (name "Net-(U$7-BOTTOMRIGHT)") (class "Default")
      (node (ref "R30") (pin "2") (pinfunction "2_2") (pintype "passive"))
      (node (ref "R30") (pin "3") (pinfunction "2_3") (pintype "passive"))
      (node (ref "U$7") (pin "PBR") (pinfunction "BOTTOMRIGHT_PBR") (pintype "input"))
    )
    (net (code "67") (name "Net-(U$7-MIDDLE)") (class "Default")
      (node (ref "R27") (pin "2") (pinfunction "2_2") (pintype "passive"))
      (node (ref "R27") (pin "3") (pinfunction "2_3") (pintype "passive"))
      (node (ref "U$7") (pin "PM") (pinfunction "MIDDLE_PM") (pintype "input"))
    )
    (net (code "68") (name "Net-(U$7-TOP)") (class "Default")
      (node (ref "R29") (pin "2") (pinfunction "2_2") (pintype "passive"))
      (node (ref "R29") (pin "3") (pinfunction "2_3") (pintype "passive"))
      (node (ref "U$7") (pin "PT") (pinfunction "TOP_PT") (pintype "input"))
    )
    (net (code "69") (name "Net-(U$7-TOPLEFT)") (class "Default")
      (node (ref "R28") (pin "2") (pinfunction "2_2") (pintype "passive"))
      (node (ref "R28") (pin "3") (pinfunction "2_3") (pintype "passive"))
      (node (ref "U$7") (pin "PTL") (pinfunction "TOPLEFT_PTL") (pintype "input"))
    )
    (net (code "70") (name "Net-(U$7-TOPRIGHT)") (class "Default")
      (node (ref "R31") (pin "2") (pinfunction "2_2") (pintype "passive"))
      (node (ref "R31") (pin "3") (pinfunction "2_3") (pintype "passive"))
      (node (ref "U$7") (pin "PTR") (pinfunction "TOPRIGHT_PTR") (pintype "input"))
    )
    (net (code "71") (name "Net-(UC1-QH*-Pad9)") (class "Default")
      (node (ref "UC1") (pin "9") (pinfunction "QH*_9") (pintype "tri_state"))
      (node (ref "UC1") (pin "S9") (pinfunction "QH*_S9") (pintype "tri_state"))
      (node (ref "UC2") (pin "14") (pinfunction "SER_14") (pintype "input"))
      (node (ref "UC2") (pin "S14") (pinfunction "SER_S14") (pintype "input"))
    )
    (net (code "72") (name "Net-(UC2-QH*-Pad9)") (class "Default")
      (node (ref "UC2") (pin "9") (pinfunction "QH*_9") (pintype "tri_state"))
      (node (ref "UC2") (pin "S9") (pinfunction "QH*_S9") (pintype "tri_state"))
      (node (ref "UC3") (pin "14") (pinfunction "SER_14") (pintype "input"))
      (node (ref "UC3") (pin "S14") (pinfunction "SER_S14") (pintype "input"))
    )
    (net (code "73") (name "Net-(UC3-QH*-Pad9)") (class "Default")
      (node (ref "UC3") (pin "9") (pinfunction "QH*_9") (pintype "tri_state"))
      (node (ref "UC3") (pin "S9") (pinfunction "QH*_S9") (pintype "tri_state"))
      (node (ref "UC4") (pin "14") (pinfunction "SER_14") (pintype "input"))
      (node (ref "UC4") (pin "S14") (pinfunction "SER_S14") (pintype "input"))
    )
  )
)
